# BlinkyBall-switchedcap.net
KiCad netlist of a schematic drawn in EAGLE
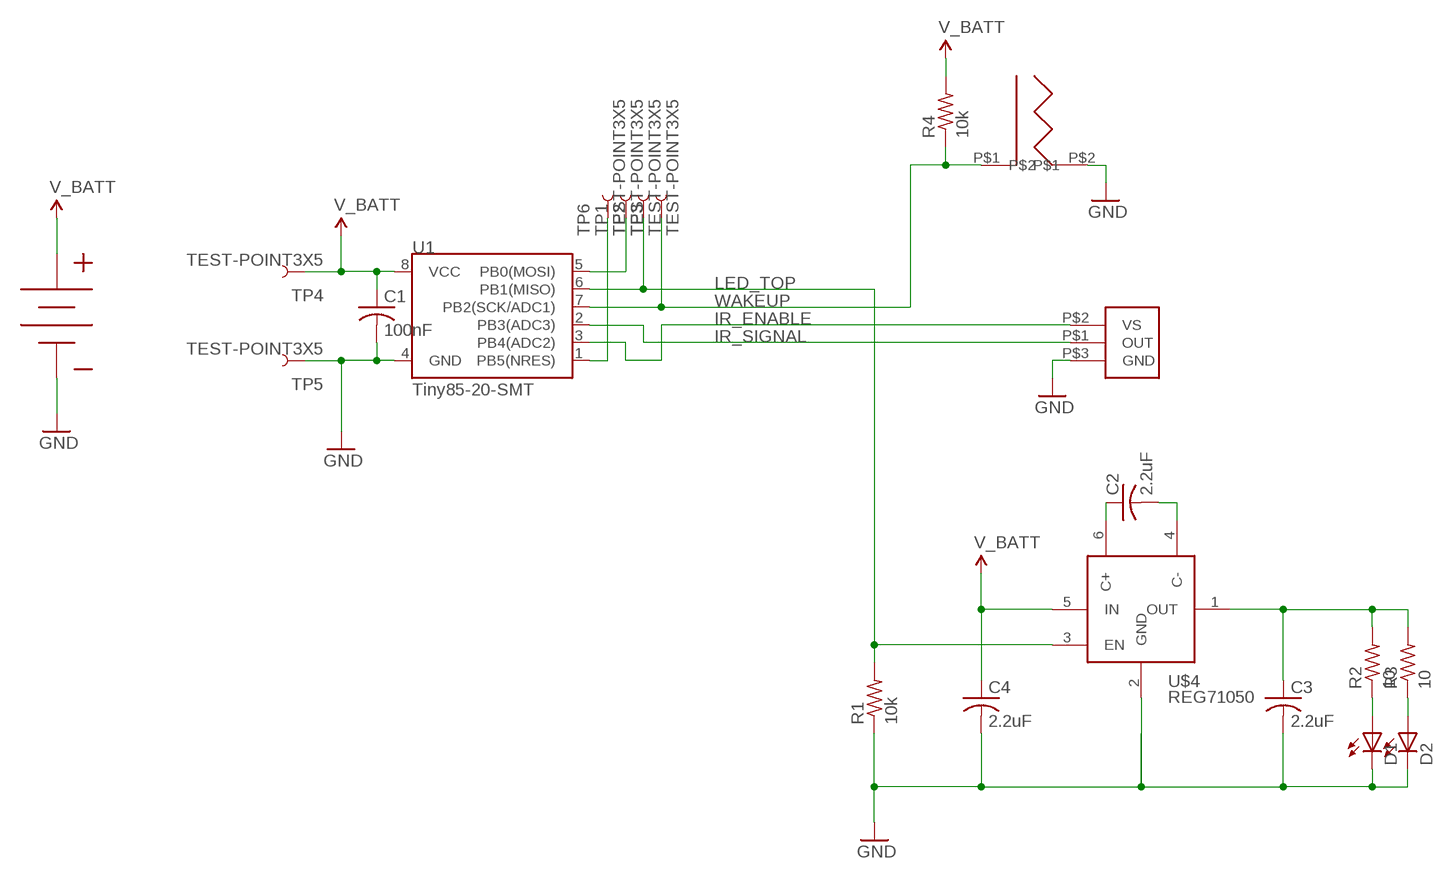
[diagram p0: schematic, sheet 1]

(export (version "E")
  (design (tool "Eeschema 10.0.6"))
  (components
    (comp (ref "C1")
      (value "100nF")
      (footprint "eagle-import:C0603")
      (libsource (lib "eagle-import") (part "C-USC0603"))
    )
    (comp (ref "C2")
      (value "2.2uF")
      (footprint "eagle-import:C0603")
      (libsource (lib "eagle-import") (part "C-USC0603"))
    )
    (comp (ref "C3")
      (value "2.2uF")
      (footprint "eagle-import:C0603")
      (libsource (lib "eagle-import") (part "C-USC0603"))
    )
    (comp (ref "C4")
      (value "2.2uF")
      (footprint "eagle-import:C0603")
      (libsource (lib "eagle-import") (part "C-USC0603"))
    )
    (comp (ref "D1")
      (value "LED5MM")
      (footprint "eagle-import:LED5MM")
      (libsource (lib "eagle-import") (part "LED5MM"))
    )
    (comp (ref "D2")
      (value "LED5MM")
      (footprint "eagle-import:LED5MM")
      (libsource (lib "eagle-import") (part "LED5MM"))
    )
    (comp (ref "R1")
      (value "10k")
      (footprint "eagle-import:R0603")
      (libsource (lib "eagle-import") (part "R-US_R0603"))
    )
    (comp (ref "R2")
      (value "10")
      (footprint "eagle-import:R0603")
      (libsource (lib "eagle-import") (part "R-US_R0603"))
    )
    (comp (ref "R3")
      (value "10")
      (footprint "eagle-import:R0603")
      (libsource (lib "eagle-import") (part "R-US_R0603"))
    )
    (comp (ref "R4")
      (value "10k")
      (footprint "eagle-import:R0603")
      (libsource (lib "eagle-import") (part "R-US_R0603"))
    )
    (comp (ref "TP1")
      (value "TEST-POINT3X5")
      (footprint "eagle-import:PAD.03X.05")
      (libsource (lib "eagle-import") (part "TEST-POINT3X5"))
    )
    (comp (ref "TP2")
      (value "TEST-POINT3X5")
      (footprint "eagle-import:PAD.03X.05")
      (libsource (lib "eagle-import") (part "TEST-POINT3X5"))
    )
    (comp (ref "TP3")
      (value "TEST-POINT3X5")
      (footprint "eagle-import:PAD.03X.05")
      (libsource (lib "eagle-import") (part "TEST-POINT3X5"))
    )
    (comp (ref "TP4")
      (value "TEST-POINT3X5")
      (footprint "eagle-import:PAD.03X.05")
      (libsource (lib "eagle-import") (part "TEST-POINT3X5"))
    )
    (comp (ref "TP5")
      (value "TEST-POINT3X5")
      (footprint "eagle-import:PAD.03X.05")
      (libsource (lib "eagle-import") (part "TEST-POINT3X5"))
    )
    (comp (ref "TP6")
      (value "TEST-POINT3X5")
      (footprint "eagle-import:PAD.03X.05")
      (libsource (lib "eagle-import") (part "TEST-POINT3X5"))
    )
    (comp (ref "U$1")
      (value "BATTERY_BUTTON_CELLAG3")
      (footprint "eagle-import:BATTERY_COVER_AG3")
      (libsource (lib "eagle-import") (part "BATTERY_BUTTON_CELLAG3"))
    )
    (comp (ref "U$3")
      (value "SW-18015P")
      (footprint "eagle-import:SW-18015P")
      (libsource (lib "eagle-import") (part "SW-18015P"))
    )
    (comp (ref "U$4")
      (value "REG71050")
      (footprint "eagle-import:SOT23-6")
      (libsource (lib "eagle-import") (part "REG71050"))
    )
    (comp (ref "U$5")
      (value "TSOP321")
      (footprint "eagle-import:TSOP321")
      (libsource (lib "eagle-import") (part "TSOP321"))
    )
    (comp (ref "U1")
      (value "Tiny85-20-SMT")
      (footprint "eagle-import:SO08-EIAJ")
      (libsource (lib "eagle-import") (part "ATTINY45TINY85-20-SMT"))
    )
  )
  (nets
    (net (code "1") (name "/IR_ENABLE") (class "Default")
      (node (ref "U$5") (pin "P$2") (pinfunction "VS_P$2") (pintype "bidirectional"))
      (node (ref "U1") (pin "3") (pinfunction "PB4(ADC2)_3") (pintype "bidirectional"))
    )
    (net (code "2") (name "/IR_SIGNAL") (class "Default")
      (node (ref "U$5") (pin "P$1") (pinfunction "OUT_P$1") (pintype "bidirectional"))
      (node (ref "U1") (pin "2") (pinfunction "PB3(ADC3)_2") (pintype "bidirectional"))
    )
    (net (code "3") (name "/LED_TOP") (class "Default")
      (node (ref "R1") (pin "2") (pinfunction "2_2") (pintype "passive"))
      (node (ref "TP2") (pin "P$1") (pinfunction "1_P$1") (pintype "bidirectional"))
      (node (ref "U$4") (pin "3") (pinfunction "EN_3") (pintype "bidirectional"))
      (node (ref "U1") (pin "6") (pinfunction "PB1(MISO)_6") (pintype "bidirectional"))
    )
    (net (code "4") (name "/WAKEUP") (class "Default")
      (node (ref "R4") (pin "1") (pinfunction "1_1") (pintype "passive"))
      (node (ref "TP3") (pin "P$1") (pinfunction "1_P$1") (pintype "bidirectional"))
      (node (ref "U$3") (pin "P$1") (pinfunction "P$1_P$1") (pintype "bidirectional"))
      (node (ref "U1") (pin "7") (pinfunction "PB2(SCK/ADC1)_7") (pintype "bidirectional"))
    )
    (net (code "5") (name "GND") (class "Default")
      (node (ref "C1") (pin "2") (pinfunction "2_2") (pintype "passive"))
      (node (ref "C3") (pin "2") (pinfunction "2_2") (pintype "passive"))
      (node (ref "C4") (pin "2") (pinfunction "2_2") (pintype "passive"))
      (node (ref "D1") (pin "K") (pinfunction "C_K") (pintype "passive"))
      (node (ref "D2") (pin "K") (pinfunction "C_K") (pintype "passive"))
      (node (ref "R1") (pin "1") (pinfunction "1_1") (pintype "passive"))
      (node (ref "TP5") (pin "P$1") (pinfunction "1_P$1") (pintype "bidirectional"))
      (node (ref "U$1") (pin "-") (pinfunction "-_-") (pintype "power_in"))
      (node (ref "U$3") (pin "P$2") (pinfunction "P$2_P$2") (pintype "bidirectional"))
      (node (ref "U$4") (pin "2") (pinfunction "GND_2") (pintype "bidirectional"))
      (node (ref "U$5") (pin "P$3") (pinfunction "GND_P$3") (pintype "bidirectional"))
      (node (ref "U1") (pin "4") (pinfunction "GND_4") (pintype "bidirectional"))
    )
    (net (code "6") (name "Net-(D1-PadA)") (class "Default")
      (node (ref "D1") (pin "A") (pinfunction "A_A") (pintype "passive"))
      (node (ref "R2") (pin "1") (pinfunction "1_1") (pintype "passive"))
    )
    (net (code "7") (name "Net-(D2-PadA)") (class "Default")
      (node (ref "D2") (pin "A") (pinfunction "A_A") (pintype "passive"))
      (node (ref "R3") (pin "1") (pinfunction "1_1") (pintype "passive"))
    )
    (net (code "8") (name "Net-(TP1-1)") (class "Default")
      (node (ref "TP1") (pin "P$1") (pinfunction "1_P$1") (pintype "bidirectional"))
      (node (ref "U1") (pin "5") (pinfunction "PB0(MOSI)_5") (pintype "bidirectional"))
    )
    (net (code "9") (name "Net-(TP6-1)") (class "Default")
      (node (ref "TP6") (pin "P$1") (pinfunction "1_P$1") (pintype "bidirectional"))
      (node (ref "U1") (pin "1") (pinfunction "PB5(NRES)_1") (pintype "bidirectional"))
    )
    (net (code "10") (name "Net-(U$4-C+)") (class "Default")
      (node (ref "C2") (pin "1") (pinfunction "1_1") (pintype "passive"))
      (node (ref "U$4") (pin "6") (pinfunction "C+_6") (pintype "bidirectional"))
    )
    (net (code "11") (name "Net-(U$4-C-)") (class "Default")
      (node (ref "C2") (pin "2") (pinfunction "2_2") (pintype "passive"))
      (node (ref "U$4") (pin "4") (pinfunction "C-_4") (pintype "bidirectional"))
    )
    (net (code "12") (name "Net-(U$4-OUT)") (class "Default")
      (node (ref "C3") (pin "1") (pinfunction "1_1") (pintype "passive"))
      (node (ref "R2") (pin "2") (pinfunction "2_2") (pintype "passive"))
      (node (ref "R3") (pin "2") (pinfunction "2_2") (pintype "passive"))
      (node (ref "U$4") (pin "1") (pinfunction "OUT_1") (pintype "bidirectional"))
    )
    (net (code "13") (name "V_BATT") (class "Default")
      (node (ref "C1") (pin "1") (pinfunction "1_1") (pintype "passive"))
      (node (ref "C4") (pin "1") (pinfunction "1_1") (pintype "passive"))
      (node (ref "R4") (pin "2") (pinfunction "2_2") (pintype "passive"))
      (node (ref "TP4") (pin "P$1") (pinfunction "1_P$1") (pintype "bidirectional"))
      (node (ref "U$1") (pin "+1") (pinfunction "+_+1") (pintype "power_in"))
      (node (ref "U$1") (pin "+2") (pinfunction "+_+2") (pintype "power_in"))
      (node (ref "U$1") (pin "+3") (pinfunction "+_+3") (pintype "power_in"))
      (node (ref "U$1") (pin "+4") (pinfunction "+_+4") (pintype "power_in"))
      (node (ref "U$4") (pin "5") (pinfunction "IN_5") (pintype "bidirectional"))
      (node (ref "U1") (pin "8") (pinfunction "VCC_8") (pintype "bidirectional"))
    )
  )
)
